# motherboard.net
KiCad netlist of a schematic drawn in EAGLE
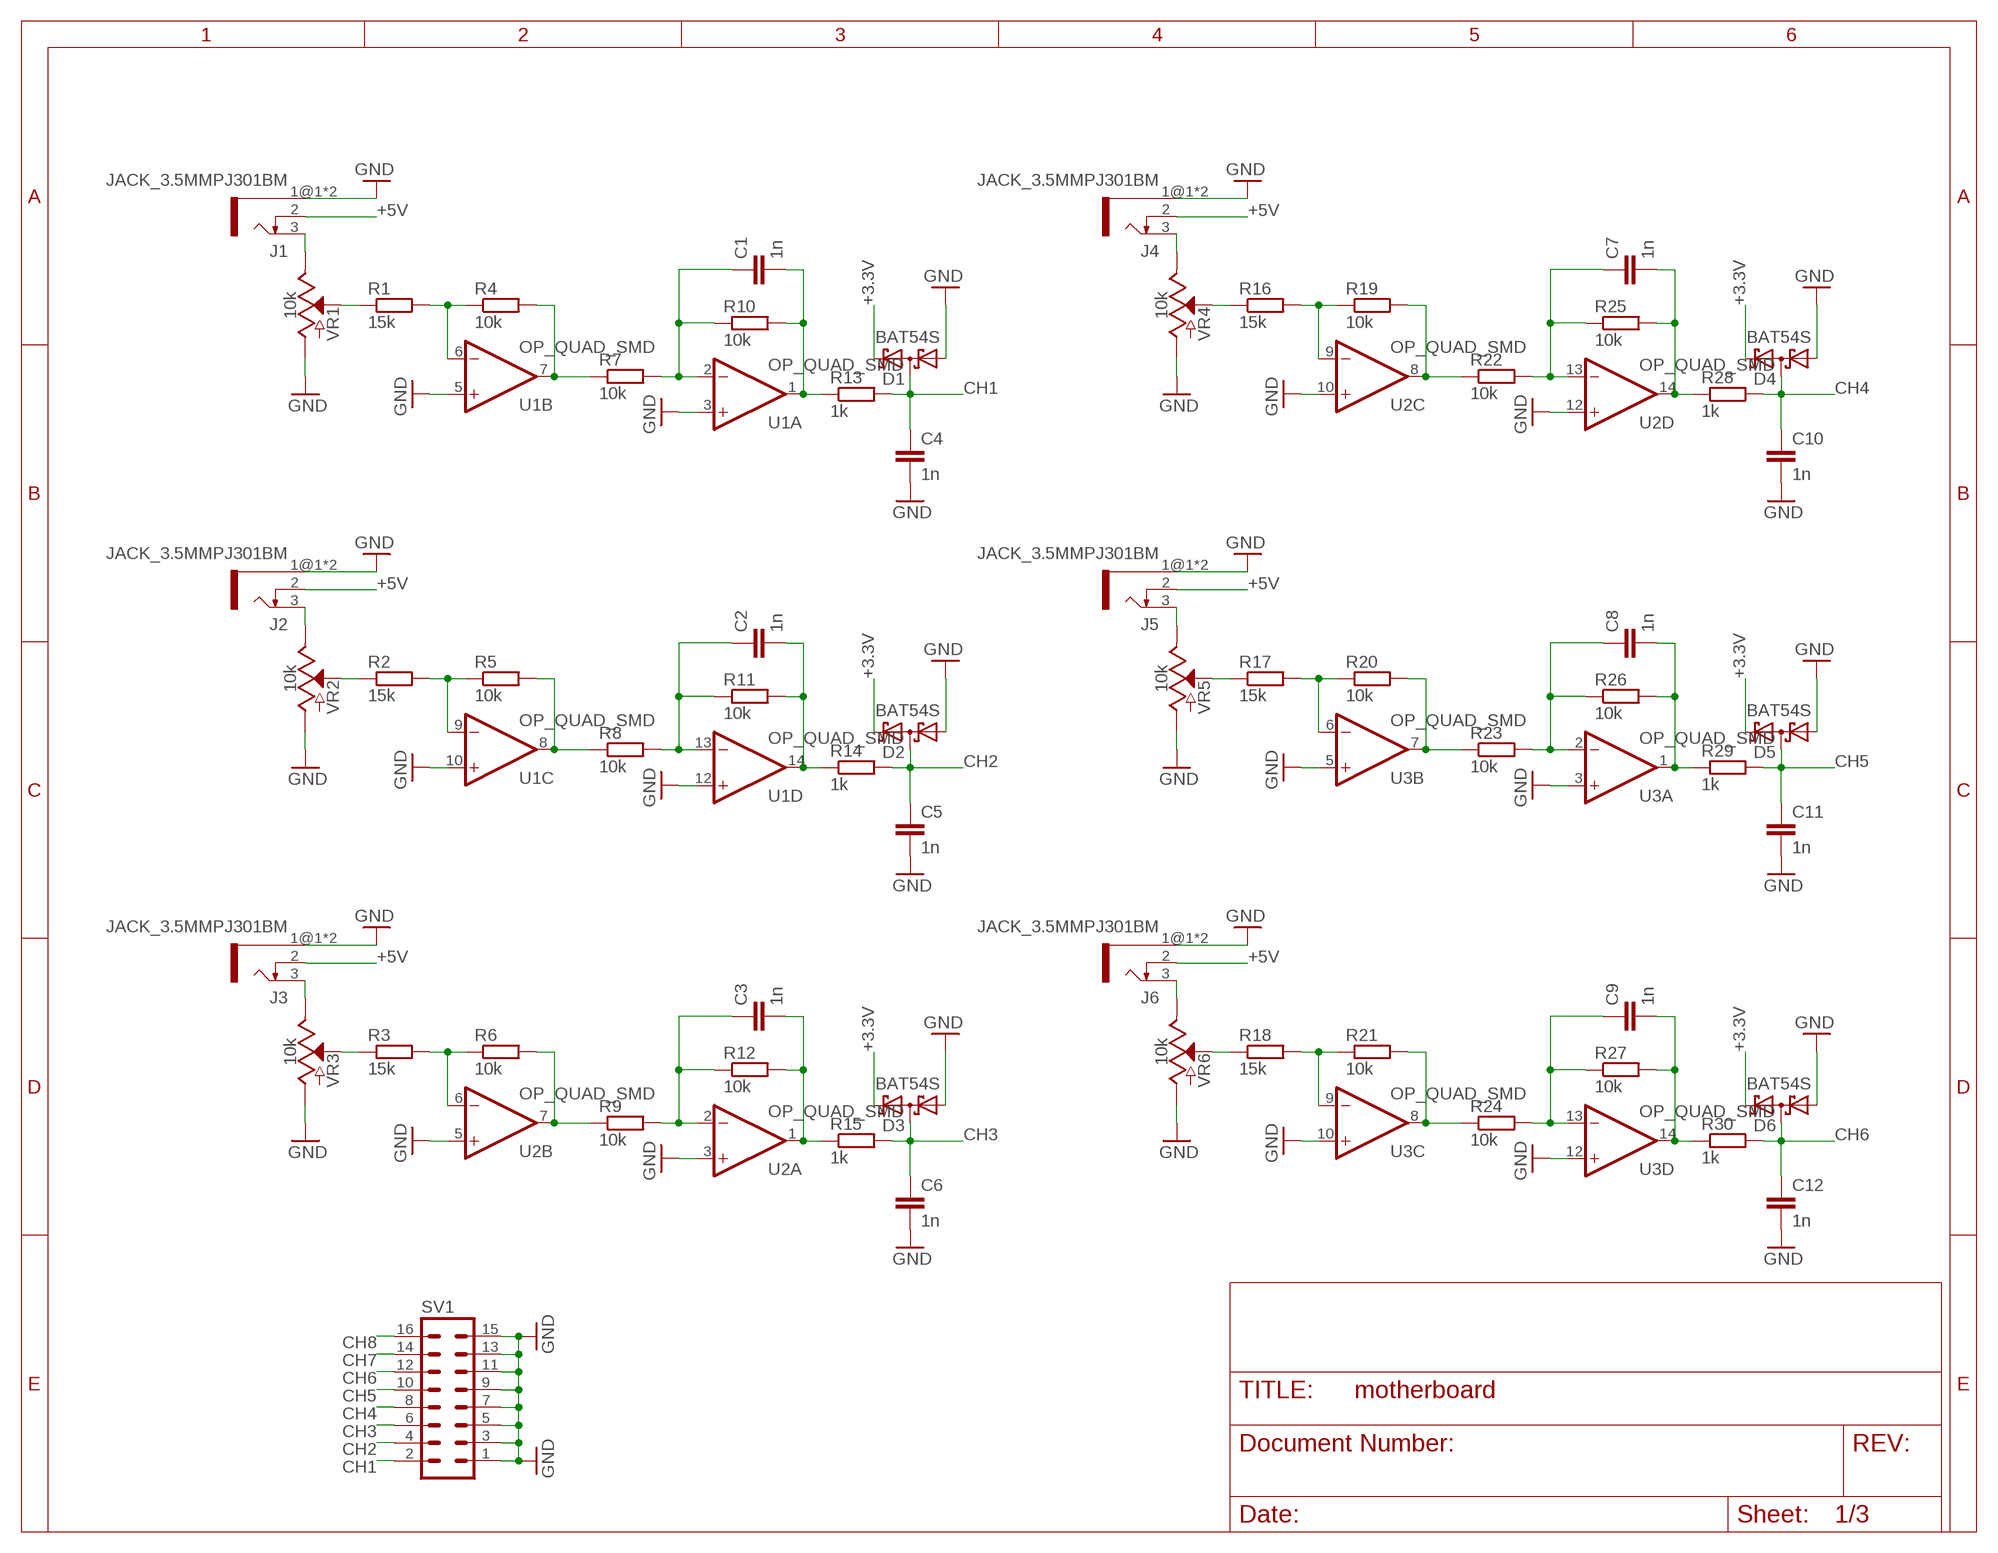
[diagram p0: schematic, sheet 1]
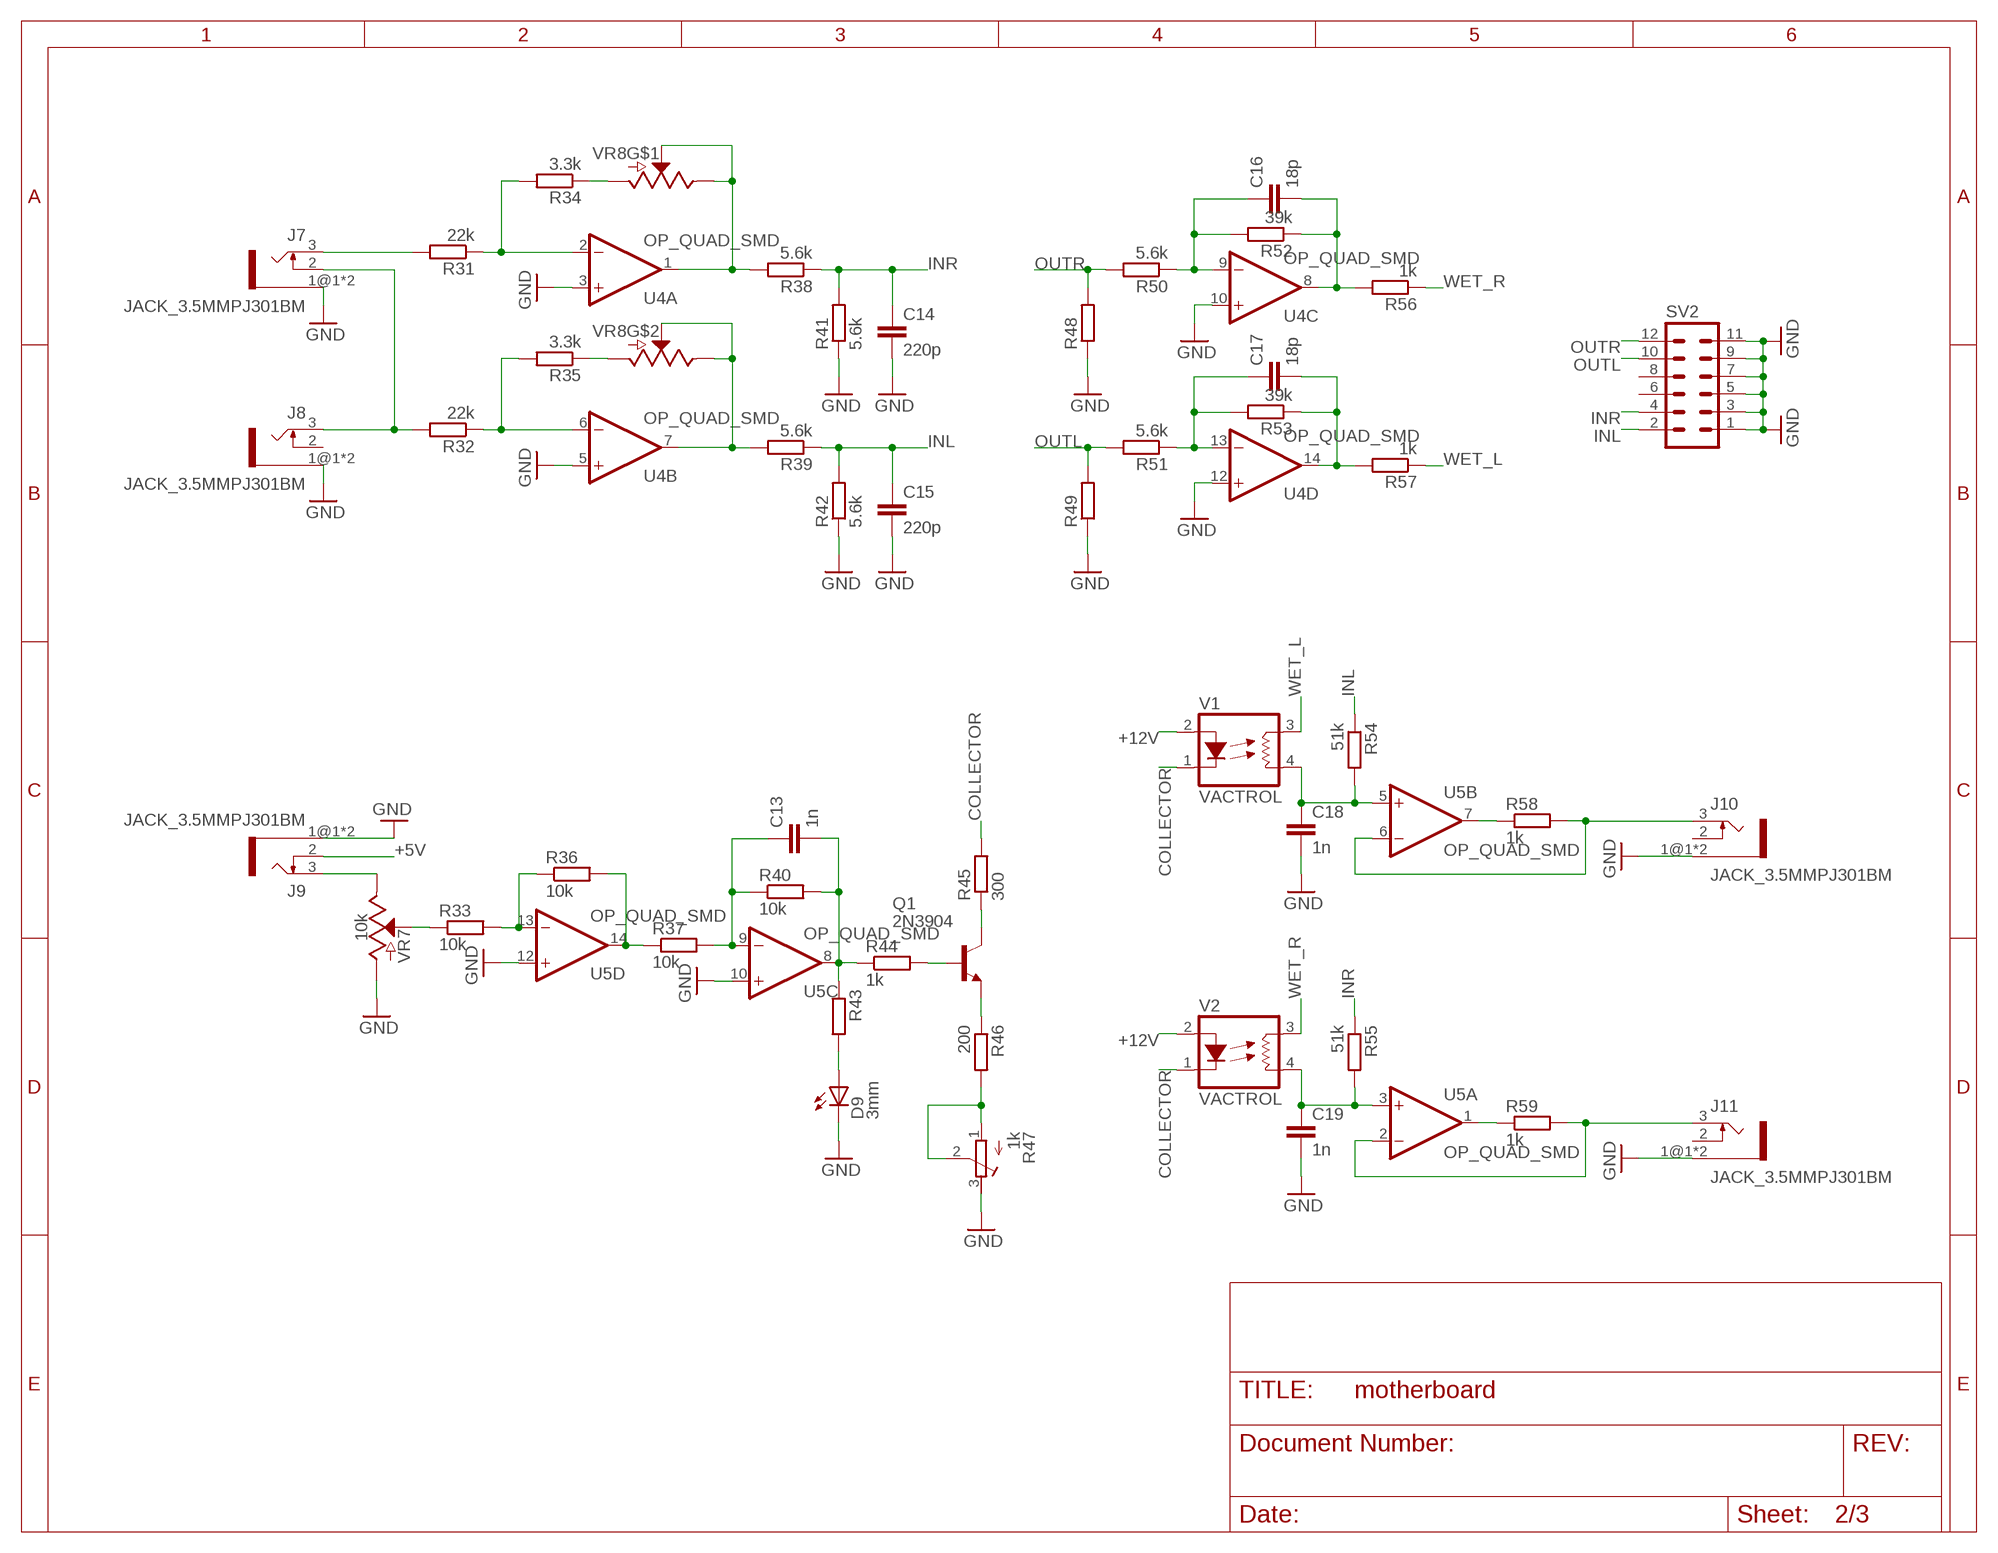
[diagram p1: schematic, sheet 2]
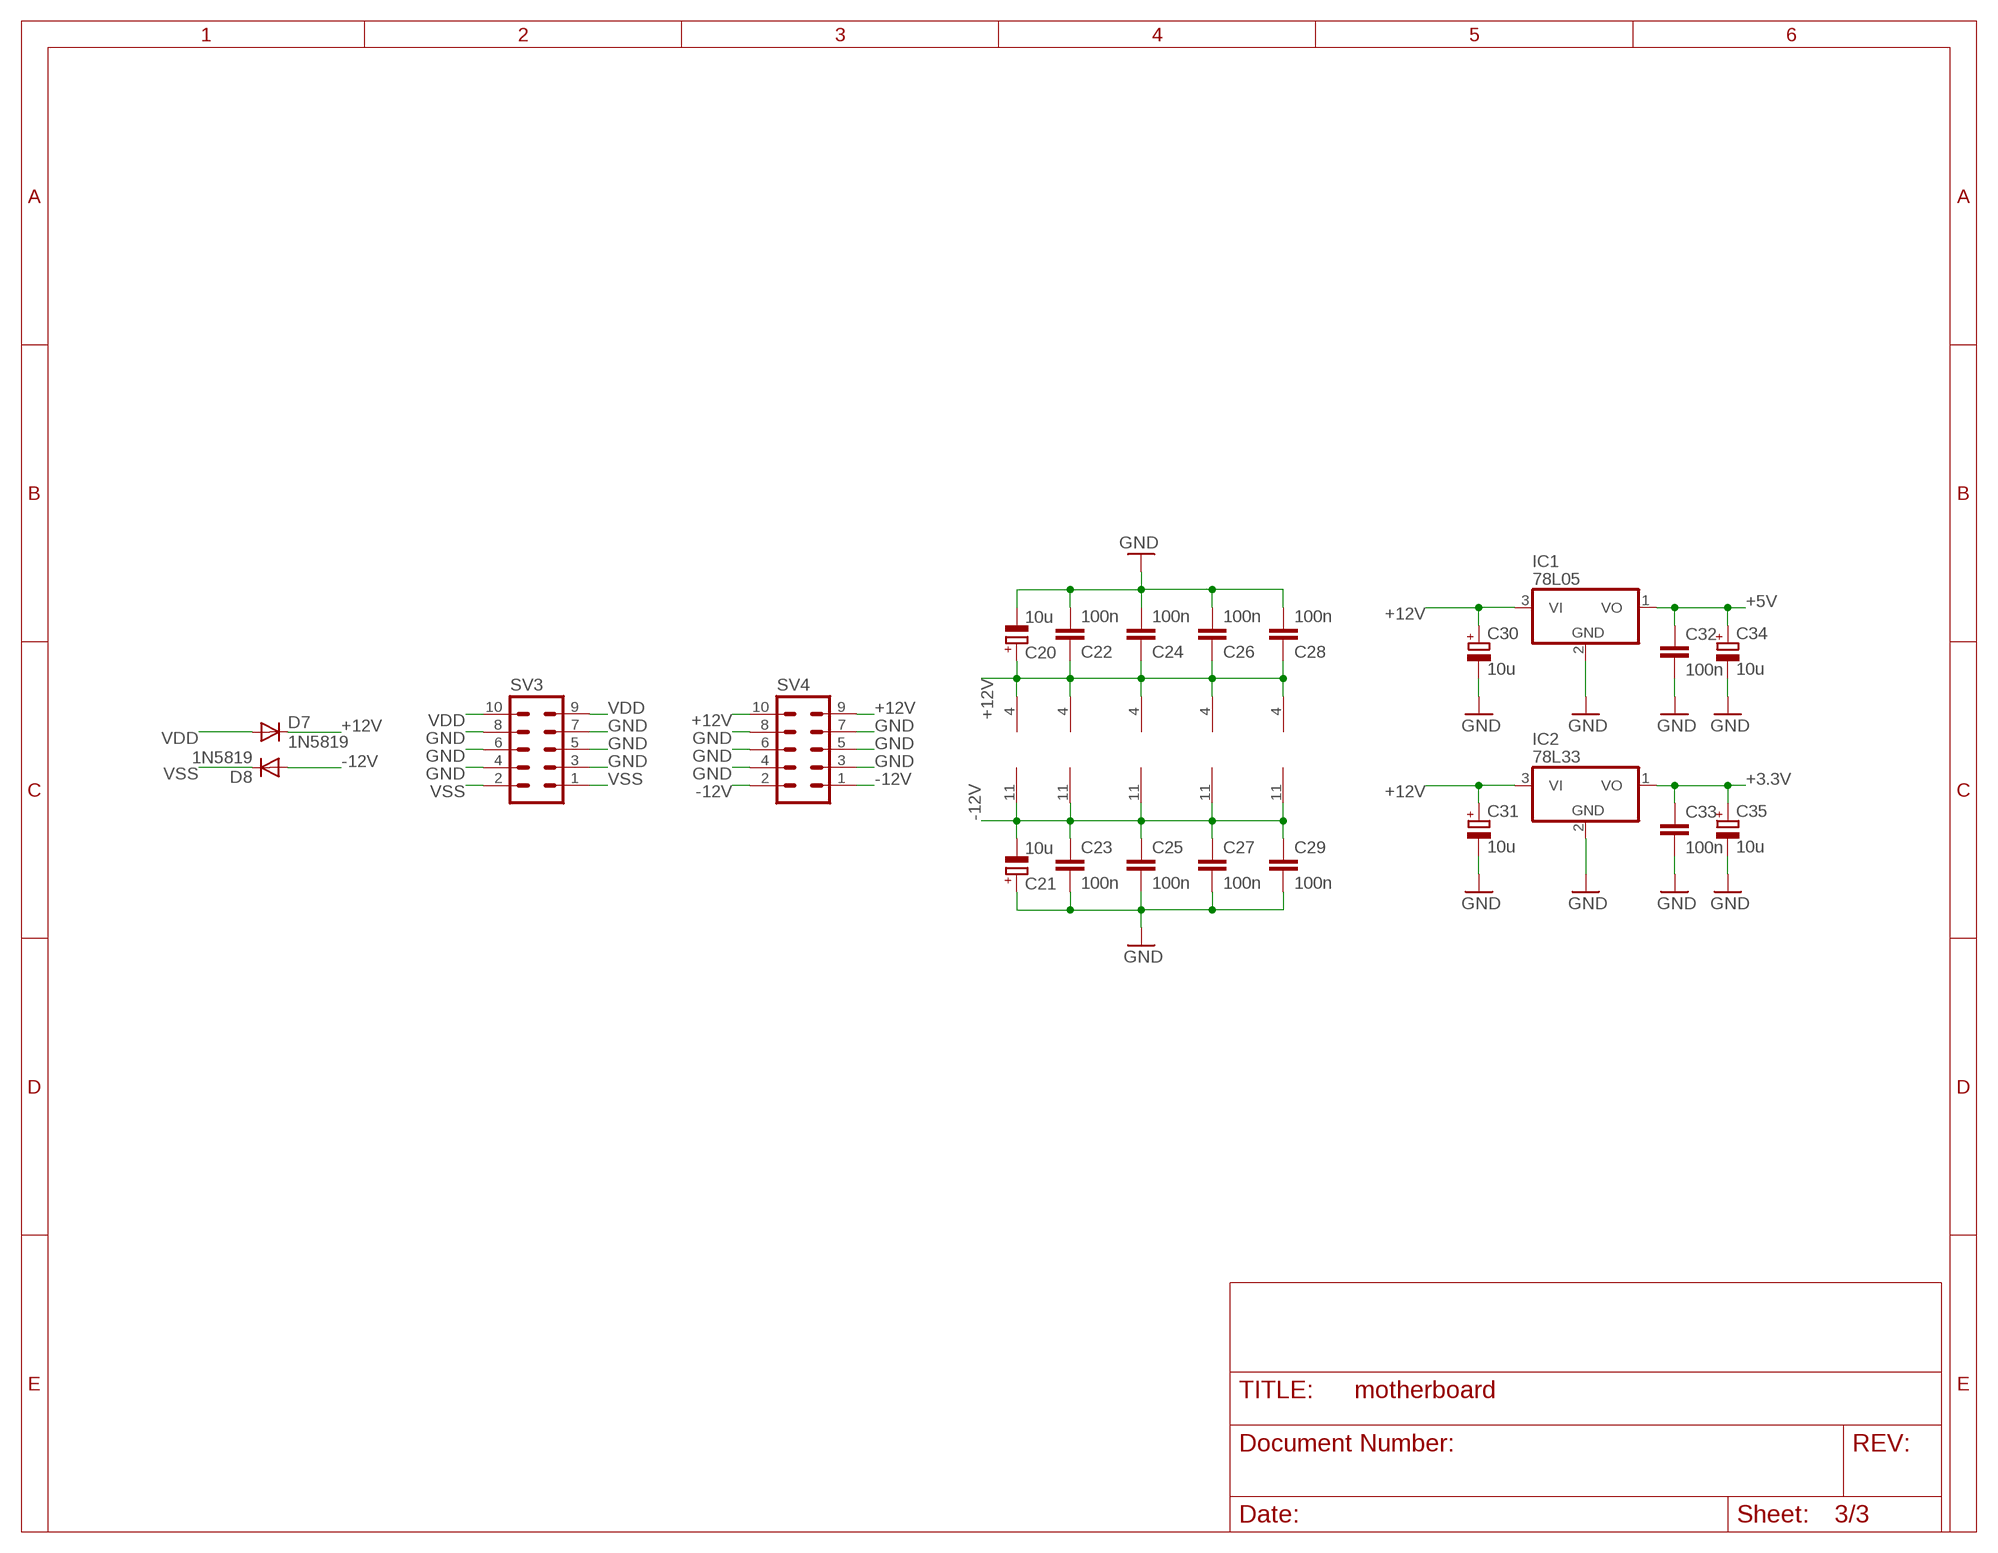
[diagram p2: schematic, sheet 3]

(export (version "E")
  (design (tool "Eeschema 10.0.6"))
  (components
    (comp (ref "C20")
      (value "10u")
      (footprint "eagle-import:E2,5-6")
      (libsource (lib "eagle-import") (part "CPOL-EUE2.5-6"))
    )
    (comp (ref "C21")
      (value "10u")
      (footprint "eagle-import:E2,5-6")
      (libsource (lib "eagle-import") (part "CPOL-EUE2.5-6"))
    )
    (comp (ref "C22")
      (value "100n")
      (footprint "eagle-import:C5B3.5")
      (libsource (lib "eagle-import") (part "C5/3.5"))
    )
    (comp (ref "C23")
      (value "100n")
      (footprint "eagle-import:C5B3.5")
      (libsource (lib "eagle-import") (part "C5/3.5"))
    )
    (comp (ref "C24")
      (value "100n")
      (footprint "eagle-import:C5B3.5")
      (libsource (lib "eagle-import") (part "C5/3.5"))
    )
    (comp (ref "C25")
      (value "100n")
      (footprint "eagle-import:C5B3.5")
      (libsource (lib "eagle-import") (part "C5/3.5"))
    )
    (comp (ref "C26")
      (value "100n")
      (footprint "eagle-import:C5B3.5")
      (libsource (lib "eagle-import") (part "C5/3.5"))
    )
    (comp (ref "C27")
      (value "100n")
      (footprint "eagle-import:C5B3.5")
      (libsource (lib "eagle-import") (part "C5/3.5"))
    )
    (comp (ref "C28")
      (value "100n")
      (footprint "eagle-import:C5B3.5")
      (libsource (lib "eagle-import") (part "C5/3.5"))
    )
    (comp (ref "C29")
      (value "100n")
      (footprint "eagle-import:C5B3.5")
      (libsource (lib "eagle-import") (part "C5/3.5"))
    )
    (comp (ref "C30")
      (value "10u")
      (footprint "eagle-import:E2,5-6")
      (libsource (lib "eagle-import") (part "CPOL-EUE2.5-6"))
    )
    (comp (ref "C31")
      (value "10u")
      (footprint "eagle-import:E2,5-6")
      (libsource (lib "eagle-import") (part "CPOL-EUE2.5-6"))
    )
    (comp (ref "C32")
      (value "100n")
      (footprint "eagle-import:C5B3.5")
      (libsource (lib "eagle-import") (part "C5/3.5"))
    )
    (comp (ref "C33")
      (value "100n")
      (footprint "eagle-import:C5B3.5")
      (libsource (lib "eagle-import") (part "C5/3.5"))
    )
    (comp (ref "C34")
      (value "10u")
      (footprint "eagle-import:E2,5-6")
      (libsource (lib "eagle-import") (part "CPOL-EUE2.5-6"))
    )
    (comp (ref "C35")
      (value "10u")
      (footprint "eagle-import:E2,5-6")
      (libsource (lib "eagle-import") (part "CPOL-EUE2.5-6"))
    )
    (comp (ref "D7")
      (value "1N5819")
      (footprint "eagle-import:SOD-123_MINI-SMA")
      (libsource (lib "eagle-import") (part "CGRM400-G1"))
    )
    (comp (ref "D8")
      (value "1N5819")
      (footprint "eagle-import:SOD-123_MINI-SMA")
      (libsource (lib "eagle-import") (part "CGRM400-G1"))
    )
    (comp (ref "IC1")
      (value "78L05")
      (footprint "eagle-import:TO92")
      (libsource (lib "eagle-import") (part "78ZL05"))
    )
    (comp (ref "IC2")
      (value "78L33")
      (footprint "eagle-import:TO92")
      (libsource (lib "eagle-import") (part "78ZL05"))
    )
    (comp (ref "SV3")
      (value "MA05-2")
      (footprint "eagle-import:MA05-2")
      (libsource (lib "eagle-import") (part "MA05-2"))
    )
    (comp (ref "SV4")
      (value "MA05-2")
      (footprint "eagle-import:MA05-2")
      (libsource (lib "eagle-import") (part "MA05-2"))
    )
    (comp (ref "U1")
      (value "OP_QUAD_SMD")
      (footprint "eagle-import:SO14")
      (libsource (lib "eagle-import") (part "OP_QUAD_SMD"))
    )
    (comp (ref "U2")
      (value "OP_QUAD_SMD")
      (footprint "eagle-import:SO14")
      (libsource (lib "eagle-import") (part "OP_QUAD_SMD"))
    )
    (comp (ref "U3")
      (value "OP_QUAD_SMD")
      (footprint "eagle-import:SO14")
      (libsource (lib "eagle-import") (part "OP_QUAD_SMD"))
    )
    (comp (ref "U4")
      (value "OP_QUAD_SMD")
      (footprint "eagle-import:SO14")
      (libsource (lib "eagle-import") (part "OP_QUAD_SMD"))
    )
    (comp (ref "U5")
      (value "OP_QUAD_SMD")
      (footprint "eagle-import:SO14")
      (libsource (lib "eagle-import") (part "OP_QUAD_SMD"))
    )
    (comp (ref "C1")
      (value "1n")
      (footprint "eagle-import:C0603")
      (libsource (lib "eagle-import") (part "CC0603"))
    )
    (comp (ref "C2")
      (value "1n")
      (footprint "eagle-import:C0603")
      (libsource (lib "eagle-import") (part "CC0603"))
    )
    (comp (ref "C3")
      (value "1n")
      (footprint "eagle-import:C0603")
      (libsource (lib "eagle-import") (part "CC0603"))
    )
    (comp (ref "C4")
      (value "1n")
      (footprint "eagle-import:C0603")
      (libsource (lib "eagle-import") (part "CC0603"))
    )
    (comp (ref "C5")
      (value "1n")
      (footprint "eagle-import:C0603")
      (libsource (lib "eagle-import") (part "CC0603"))
    )
    (comp (ref "C6")
      (value "1n")
      (footprint "eagle-import:C0603")
      (libsource (lib "eagle-import") (part "CC0603"))
    )
    (comp (ref "C7")
      (value "1n")
      (footprint "eagle-import:C0603")
      (libsource (lib "eagle-import") (part "CC0603"))
    )
    (comp (ref "C8")
      (value "1n")
      (footprint "eagle-import:C0603")
      (libsource (lib "eagle-import") (part "CC0603"))
    )
    (comp (ref "C9")
      (value "1n")
      (footprint "eagle-import:C0603")
      (libsource (lib "eagle-import") (part "CC0603"))
    )
    (comp (ref "C10")
      (value "1n")
      (footprint "eagle-import:C0603")
      (libsource (lib "eagle-import") (part "CC0603"))
    )
    (comp (ref "C11")
      (value "1n")
      (footprint "eagle-import:C0603")
      (libsource (lib "eagle-import") (part "CC0603"))
    )
    (comp (ref "C12")
      (value "1n")
      (footprint "eagle-import:C0603")
      (libsource (lib "eagle-import") (part "CC0603"))
    )
    (comp (ref "D1")
      (value "BAT54S")
      (footprint "eagle-import:SOT23")
      (libsource (lib "eagle-import") (part "BAT54S"))
    )
    (comp (ref "D2")
      (value "BAT54S")
      (footprint "eagle-import:SOT23")
      (libsource (lib "eagle-import") (part "BAT54S"))
    )
    (comp (ref "D3")
      (value "BAT54S")
      (footprint "eagle-import:SOT23")
      (libsource (lib "eagle-import") (part "BAT54S"))
    )
    (comp (ref "D4")
      (value "BAT54S")
      (footprint "eagle-import:SOT23")
      (libsource (lib "eagle-import") (part "BAT54S"))
    )
    (comp (ref "D5")
      (value "BAT54S")
      (footprint "eagle-import:SOT23")
      (libsource (lib "eagle-import") (part "BAT54S"))
    )
    (comp (ref "D6")
      (value "BAT54S")
      (footprint "eagle-import:SOT23")
      (libsource (lib "eagle-import") (part "BAT54S"))
    )
    (comp (ref "J1")
      (value "JACK_3.5MMPJ301BM")
      (footprint "eagle-import:PJ301BM_JACK")
      (libsource (lib "eagle-import") (part "JACK_3.5MMPJ301BM"))
    )
    (comp (ref "J2")
      (value "JACK_3.5MMPJ301BM")
      (footprint "eagle-import:PJ301BM_JACK")
      (libsource (lib "eagle-import") (part "JACK_3.5MMPJ301BM"))
    )
    (comp (ref "J3")
      (value "JACK_3.5MMPJ301BM")
      (footprint "eagle-import:PJ301BM_JACK")
      (libsource (lib "eagle-import") (part "JACK_3.5MMPJ301BM"))
    )
    (comp (ref "J4")
      (value "JACK_3.5MMPJ301BM")
      (footprint "eagle-import:PJ301BM_JACK")
      (libsource (lib "eagle-import") (part "JACK_3.5MMPJ301BM"))
    )
    (comp (ref "J5")
      (value "JACK_3.5MMPJ301BM")
      (footprint "eagle-import:PJ301BM_JACK")
      (libsource (lib "eagle-import") (part "JACK_3.5MMPJ301BM"))
    )
    (comp (ref "J6")
      (value "JACK_3.5MMPJ301BM")
      (footprint "eagle-import:PJ301BM_JACK")
      (libsource (lib "eagle-import") (part "JACK_3.5MMPJ301BM"))
    )
    (comp (ref "R1")
      (value "15k")
      (footprint "eagle-import:R0603")
      (libsource (lib "eagle-import") (part "RR0603"))
    )
    (comp (ref "R2")
      (value "15k")
      (footprint "eagle-import:R0603")
      (libsource (lib "eagle-import") (part "RR0603"))
    )
    (comp (ref "R3")
      (value "15k")
      (footprint "eagle-import:R0603")
      (libsource (lib "eagle-import") (part "RR0603"))
    )
    (comp (ref "R4")
      (value "10k")
      (footprint "eagle-import:R0603")
      (libsource (lib "eagle-import") (part "RR0603"))
    )
    (comp (ref "R5")
      (value "10k")
      (footprint "eagle-import:R0603")
      (libsource (lib "eagle-import") (part "RR0603"))
    )
    (comp (ref "R6")
      (value "10k")
      (footprint "eagle-import:R0603")
      (libsource (lib "eagle-import") (part "RR0603"))
    )
    (comp (ref "R7")
      (value "10k")
      (footprint "eagle-import:R0603")
      (libsource (lib "eagle-import") (part "RR0603"))
    )
    (comp (ref "R8")
      (value "10k")
      (footprint "eagle-import:R0603")
      (libsource (lib "eagle-import") (part "RR0603"))
    )
    (comp (ref "R9")
      (value "10k")
      (footprint "eagle-import:R0603")
      (libsource (lib "eagle-import") (part "RR0603"))
    )
    (comp (ref "R10")
      (value "10k")
      (footprint "eagle-import:R0603")
      (libsource (lib "eagle-import") (part "RR0603"))
    )
    (comp (ref "R11")
      (value "10k")
      (footprint "eagle-import:R0603")
      (libsource (lib "eagle-import") (part "RR0603"))
    )
    (comp (ref "R12")
      (value "10k")
      (footprint "eagle-import:R0603")
      (libsource (lib "eagle-import") (part "RR0603"))
    )
    (comp (ref "R13")
      (value "1k")
      (footprint "eagle-import:R0603")
      (libsource (lib "eagle-import") (part "RR0603"))
    )
    (comp (ref "R14")
      (value "1k")
      (footprint "eagle-import:R0603")
      (libsource (lib "eagle-import") (part "RR0603"))
    )
    (comp (ref "R15")
      (value "1k")
      (footprint "eagle-import:R0603")
      (libsource (lib "eagle-import") (part "RR0603"))
    )
    (comp (ref "R16")
      (value "15k")
      (footprint "eagle-import:R0603")
      (libsource (lib "eagle-import") (part "RR0603"))
    )
    (comp (ref "R17")
      (value "15k")
      (footprint "eagle-import:R0603")
      (libsource (lib "eagle-import") (part "RR0603"))
    )
    (comp (ref "R18")
      (value "15k")
      (footprint "eagle-import:R0603")
      (libsource (lib "eagle-import") (part "RR0603"))
    )
    (comp (ref "R19")
      (value "10k")
      (footprint "eagle-import:R0603")
      (libsource (lib "eagle-import") (part "RR0603"))
    )
    (comp (ref "R20")
      (value "10k")
      (footprint "eagle-import:R0603")
      (libsource (lib "eagle-import") (part "RR0603"))
    )
    (comp (ref "R21")
      (value "10k")
      (footprint "eagle-import:R0603")
      (libsource (lib "eagle-import") (part "RR0603"))
    )
    (comp (ref "R22")
      (value "10k")
      (footprint "eagle-import:R0603")
      (libsource (lib "eagle-import") (part "RR0603"))
    )
    (comp (ref "R23")
      (value "10k")
      (footprint "eagle-import:R0603")
      (libsource (lib "eagle-import") (part "RR0603"))
    )
    (comp (ref "R24")
      (value "10k")
      (footprint "eagle-import:R0603")
      (libsource (lib "eagle-import") (part "RR0603"))
    )
    (comp (ref "R25")
      (value "10k")
      (footprint "eagle-import:R0603")
      (libsource (lib "eagle-import") (part "RR0603"))
    )
    (comp (ref "R26")
      (value "10k")
      (footprint "eagle-import:R0603")
      (libsource (lib "eagle-import") (part "RR0603"))
    )
    (comp (ref "R27")
      (value "10k")
      (footprint "eagle-import:R0603")
      (libsource (lib "eagle-import") (part "RR0603"))
    )
    (comp (ref "R28")
      (value "1k")
      (footprint "eagle-import:R0603")
      (libsource (lib "eagle-import") (part "RR0603"))
    )
    (comp (ref "R29")
      (value "1k")
      (footprint "eagle-import:R0603")
      (libsource (lib "eagle-import") (part "RR0603"))
    )
    (comp (ref "R30")
      (value "1k")
      (footprint "eagle-import:R0603")
      (libsource (lib "eagle-import") (part "RR0603"))
    )
    (comp (ref "SV1")
      (value "MA08-2")
      (footprint "eagle-import:MA08-2")
      (libsource (lib "eagle-import") (part "MA08-2"))
    )
    (comp (ref "VR1")
      (value "10k")
      (footprint "eagle-import:POT-PTH-ALPS-KIT")
      (libsource (lib "eagle-import") (part "POTENTIOMETER-PTH-9MM-1/20W-20%-KIT"))
    )
    (comp (ref "VR2")
      (value "10k")
      (footprint "eagle-import:POT-PTH-ALPS-KIT")
      (libsource (lib "eagle-import") (part "POTENTIOMETER-PTH-9MM-1/20W-20%-KIT"))
    )
    (comp (ref "VR3")
      (value "10k")
      (footprint "eagle-import:POT-PTH-ALPS-KIT")
      (libsource (lib "eagle-import") (part "POTENTIOMETER-PTH-9MM-1/20W-20%-KIT"))
    )
    (comp (ref "VR4")
      (value "10k")
      (footprint "eagle-import:POT-PTH-ALPS-KIT")
      (libsource (lib "eagle-import") (part "POTENTIOMETER-PTH-9MM-1/20W-20%-KIT"))
    )
    (comp (ref "VR5")
      (value "10k")
      (footprint "eagle-import:POT-PTH-ALPS-KIT")
      (libsource (lib "eagle-import") (part "POTENTIOMETER-PTH-9MM-1/20W-20%-KIT"))
    )
    (comp (ref "VR6")
      (value "10k")
      (footprint "eagle-import:POT-PTH-ALPS-KIT")
      (libsource (lib "eagle-import") (part "POTENTIOMETER-PTH-9MM-1/20W-20%-KIT"))
    )
    (comp (ref "C13")
      (value "1n")
      (footprint "eagle-import:C0603")
      (libsource (lib "eagle-import") (part "CC0603"))
    )
    (comp (ref "C14")
      (value "220p")
      (footprint "eagle-import:C0603")
      (libsource (lib "eagle-import") (part "CC0603"))
    )
    (comp (ref "C15")
      (value "220p")
      (footprint "eagle-import:C0603")
      (libsource (lib "eagle-import") (part "CC0603"))
    )
    (comp (ref "C16")
      (value "18p")
      (footprint "eagle-import:C0603")
      (libsource (lib "eagle-import") (part "CC0603"))
    )
    (comp (ref "C17")
      (value "18p")
      (footprint "eagle-import:C0603")
      (libsource (lib "eagle-import") (part "CC0603"))
    )
    (comp (ref "C18")
      (value "1n")
      (footprint "eagle-import:C0603")
      (libsource (lib "eagle-import") (part "CC0603"))
    )
    (comp (ref "C19")
      (value "1n")
      (footprint "eagle-import:C0603")
      (libsource (lib "eagle-import") (part "CC0603"))
    )
    (comp (ref "D9")
      (value "3mm")
      (footprint "eagle-import:LED3MM")
      (libsource (lib "eagle-import") (part "LED3MM"))
    )
    (comp (ref "J7")
      (value "JACK_3.5MMPJ301BM")
      (footprint "eagle-import:PJ301BM_JACK")
      (libsource (lib "eagle-import") (part "JACK_3.5MMPJ301BM"))
    )
    (comp (ref "J8")
      (value "JACK_3.5MMPJ301BM")
      (footprint "eagle-import:PJ301BM_JACK")
      (libsource (lib "eagle-import") (part "JACK_3.5MMPJ301BM"))
    )
    (comp (ref "J9")
      (value "JACK_3.5MMPJ301BM")
      (footprint "eagle-import:PJ301BM_JACK")
      (libsource (lib "eagle-import") (part "JACK_3.5MMPJ301BM"))
    )
    (comp (ref "J10")
      (value "JACK_3.5MMPJ301BM")
      (footprint "eagle-import:PJ301BM_JACK")
      (libsource (lib "eagle-import") (part "JACK_3.5MMPJ301BM"))
    )
    (comp (ref "J11")
      (value "JACK_3.5MMPJ301BM")
      (footprint "eagle-import:PJ301BM_JACK")
      (libsource (lib "eagle-import") (part "JACK_3.5MMPJ301BM"))
    )
    (comp (ref "Q1")
      (value "2N3904")
      (footprint "eagle-import:TO92")
      (libsource (lib "eagle-import") (part "2N3904"))
    )
    (comp (ref "R31")
      (value "22k")
      (footprint "eagle-import:R0603")
      (libsource (lib "eagle-import") (part "RR0603"))
    )
    (comp (ref "R32")
      (value "22k")
      (footprint "eagle-import:R0603")
      (libsource (lib "eagle-import") (part "RR0603"))
    )
    (comp (ref "R33")
      (value "10k")
      (footprint "eagle-import:R0603")
      (libsource (lib "eagle-import") (part "RR0603"))
    )
    (comp (ref "R34")
      (value "3.3k")
      (footprint "eagle-import:R0603")
      (libsource (lib "eagle-import") (part "RR0603"))
    )
    (comp (ref "R35")
      (value "3.3k")
      (footprint "eagle-import:R0603")
      (libsource (lib "eagle-import") (part "RR0603"))
    )
    (comp (ref "R36")
      (value "10k")
      (footprint "eagle-import:R0603")
      (libsource (lib "eagle-import") (part "RR0603"))
    )
    (comp (ref "R37")
      (value "10k")
      (footprint "eagle-import:R0603")
      (libsource (lib "eagle-import") (part "RR0603"))
    )
    (comp (ref "R38")
      (value "5.6k")
      (footprint "eagle-import:R0603")
      (libsource (lib "eagle-import") (part "RR0603"))
    )
    (comp (ref "R39")
      (value "5.6k")
      (footprint "eagle-import:R0603")
      (libsource (lib "eagle-import") (part "RR0603"))
    )
    (comp (ref "R40")
      (value "10k")
      (footprint "eagle-import:R0603")
      (libsource (lib "eagle-import") (part "RR0603"))
    )
    (comp (ref "R41")
      (value "5.6k")
      (footprint "eagle-import:R0603")
      (libsource (lib "eagle-import") (part "RR0603"))
    )
    (comp (ref "R42")
      (value "5.6k")
      (footprint "eagle-import:R0603")
      (libsource (lib "eagle-import") (part "RR0603"))
    )
    (comp (ref "R43")
      (value "RESISTOR10MM")
      (footprint "eagle-import:1_4W_RESISTOR")
      (libsource (lib "eagle-import") (part "RESISTOR10MM"))
    )
    (comp (ref "R44")
      (value "1k")
      (footprint "eagle-import:R0603")
      (libsource (lib "eagle-import") (part "RR0603"))
    )
    (comp (ref "R45")
      (value "300")
      (footprint "eagle-import:1_4W_RESISTOR")
      (libsource (lib "eagle-import") (part "RESISTOR10MM"))
    )
    (comp (ref "R46")
      (value "200")
      (footprint "eagle-import:R0603")
      (libsource (lib "eagle-import") (part "RR0603"))
    )
    (comp (ref "R47")
      (value "1k")
      (footprint "eagle-import:RTRIM64W")
      (libsource (lib "eagle-import") (part "R-TRIMM64W"))
    )
    (comp (ref "R48")
      (value "RR0603")
      (footprint "eagle-import:R0603")
      (libsource (lib "eagle-import") (part "RR0603"))
    )
    (comp (ref "R49")
      (value "RR0603")
      (footprint "eagle-import:R0603")
      (libsource (lib "eagle-import") (part "RR0603"))
    )
    (comp (ref "R50")
      (value "5.6k")
      (footprint "eagle-import:R0603")
      (libsource (lib "eagle-import") (part "RR0603"))
    )
    (comp (ref "R51")
      (value "5.6k")
      (footprint "eagle-import:R0603")
      (libsource (lib "eagle-import") (part "RR0603"))
    )
    (comp (ref "R52")
      (value "39k")
      (footprint "eagle-import:R0603")
      (libsource (lib "eagle-import") (part "RR0603"))
    )
    (comp (ref "R53")
      (value "39k")
      (footprint "eagle-import:R0603")
      (libsource (lib "eagle-import") (part "RR0603"))
    )
    (comp (ref "R54")
      (value "51k")
      (footprint "eagle-import:R0603")
      (libsource (lib "eagle-import") (part "RR0603"))
    )
    (comp (ref "R55")
      (value "51k")
      (footprint "eagle-import:R0603")
      (libsource (lib "eagle-import") (part "RR0603"))
    )
    (comp (ref "R56")
      (value "1k")
      (footprint "eagle-import:R0603")
      (libsource (lib "eagle-import") (part "RR0603"))
    )
    (comp (ref "R57")
      (value "1k")
      (footprint "eagle-import:R0603")
      (libsource (lib "eagle-import") (part "RR0603"))
    )
    (comp (ref "R58")
      (value "1k")
      (footprint "eagle-import:R0603")
      (libsource (lib "eagle-import") (part "RR0603"))
    )
    (comp (ref "R59")
      (value "1k")
      (footprint "eagle-import:R0603")
      (libsource (lib "eagle-import") (part "RR0603"))
    )
    (comp (ref "SV2")
      (value "MA06-2")
      (footprint "eagle-import:MA06-2")
      (libsource (lib "eagle-import") (part "MA06-2"))
    )
    (comp (ref "V1")
      (value "VACTROL")
      (footprint "eagle-import:VACTROL_4PIN_VTL5C")
      (libsource (lib "eagle-import") (part "VACTROL"))
    )
    (comp (ref "V2")
      (value "VACTROL")
      (footprint "eagle-import:VACTROL_4PIN_VTL5C")
      (libsource (lib "eagle-import") (part "VACTROL"))
    )
    (comp (ref "VR7")
      (value "10k")
      (footprint "eagle-import:POT-PTH-ALPS-KIT")
      (libsource (lib "eagle-import") (part "POTENTIOMETER-PTH-9MM-1/20W-20%-KIT"))
    )
    (comp (ref "VR8")
      (value "POTENTIOMETER_DUAL-PTH-12MM-1/20W-20%-KIT")
      (footprint "eagle-import:POT-DUAL-PTH-PANASONIC-VERT-KIT")
      (libsource (lib "eagle-import") (part "POTENTIOMETER_DUAL-PTH-12MM-1/20W-20%-KIT"))
    )
  )
  (nets
    (net (code "1") (name "+3.3V") (class "Default")
      (node (ref "C33") (pin "1") (pinfunction "1_1") (pintype "passive"))
      (node (ref "C35") (pin "+") (pinfunction "+_+") (pintype "passive"))
      (node (ref "D1") (pin "2") (pinfunction "C2_2") (pintype "passive"))
      (node (ref "D2") (pin "2") (pinfunction "C2_2") (pintype "passive"))
      (node (ref "D3") (pin "2") (pinfunction "C2_2") (pintype "passive"))
      (node (ref "D4") (pin "2") (pinfunction "C2_2") (pintype "passive"))
      (node (ref "D5") (pin "2") (pinfunction "C2_2") (pintype "passive"))
      (node (ref "D6") (pin "2") (pinfunction "C2_2") (pintype "passive"))
      (node (ref "IC2") (pin "1") (pinfunction "VO_1") (pintype "passive"))
    )
    (net (code "2") (name "+5V") (class "Default")
      (node (ref "C32") (pin "1") (pinfunction "1_1") (pintype "passive"))
      (node (ref "C34") (pin "+") (pinfunction "+_+") (pintype "passive"))
      (node (ref "IC1") (pin "1") (pinfunction "VO_1") (pintype "passive"))
      (node (ref "J1") (pin "2") (pinfunction "2_2") (pintype "passive"))
      (node (ref "J2") (pin "2") (pinfunction "2_2") (pintype "passive"))
      (node (ref "J3") (pin "2") (pinfunction "2_2") (pintype "passive"))
      (node (ref "J4") (pin "2") (pinfunction "2_2") (pintype "passive"))
      (node (ref "J5") (pin "2") (pinfunction "2_2") (pintype "passive"))
      (node (ref "J6") (pin "2") (pinfunction "2_2") (pintype "passive"))
      (node (ref "J9") (pin "2") (pinfunction "2_2") (pintype "passive"))
    )
    (net (code "3") (name "+12V") (class "Default")
      (node (ref "C20") (pin "+") (pinfunction "+_+") (pintype "passive"))
      (node (ref "C22") (pin "1") (pinfunction "1_1") (pintype "passive"))
      (node (ref "C24") (pin "1") (pinfunction "1_1") (pintype "passive"))
      (node (ref "C26") (pin "1") (pinfunction "1_1") (pintype "passive"))
      (node (ref "C28") (pin "1") (pinfunction "1_1") (pintype "passive"))
      (node (ref "C30") (pin "+") (pinfunction "+_+") (pintype "passive"))
      (node (ref "C31") (pin "+") (pinfunction "+_+") (pintype "passive"))
      (node (ref "D7") (pin "C") (pinfunction "C_C") (pintype "passive"))
      (node (ref "IC1") (pin "3") (pinfunction "VI_3") (pintype "input"))
      (node (ref "IC2") (pin "3") (pinfunction "VI_3") (pintype "input"))
      (node (ref "SV4") (pin "10") (pinfunction "10_10") (pintype "passive"))
      (node (ref "SV4") (pin "9") (pinfunction "9_9") (pintype "passive"))
      (node (ref "U1") (pin "4") (pinfunction "V+_4") (pintype "power_in"))
      (node (ref "U2") (pin "4") (pinfunction "V+_4") (pintype "power_in"))
      (node (ref "U3") (pin "4") (pinfunction "V+_4") (pintype "power_in"))
      (node (ref "U4") (pin "4") (pinfunction "V+_4") (pintype "power_in"))
      (node (ref "U5") (pin "4") (pinfunction "V+_4") (pintype "power_in"))
      (node (ref "V1") (pin "2") (pinfunction "LED+_2") (pintype "passive"))
      (node (ref "V2") (pin "2") (pinfunction "LED+_2") (pintype "passive"))
    )
    (net (code "4") (name "-12V") (class "Default")
      (node (ref "C21") (pin "-") (pinfunction "-_-") (pintype "passive"))
      (node (ref "C23") (pin "1") (pinfunction "1_1") (pintype "passive"))
      (node (ref "C25") (pin "1") (pinfunction "1_1") (pintype "passive"))
      (node (ref "C27") (pin "1") (pinfunction "1_1") (pintype "passive"))
      (node (ref "C29") (pin "1") (pinfunction "1_1") (pintype "passive"))
      (node (ref "D8") (pin "A") (pinfunction "A_A") (pintype "passive"))
      (node (ref "SV4") (pin "1") (pinfunction "1_1") (pintype "passive"))
      (node (ref "SV4") (pin "2") (pinfunction "2_2") (pintype "passive"))
      (node (ref "U1") (pin "11") (pinfunction "V-_11") (pintype "power_in"))
      (node (ref "U2") (pin "11") (pinfunction "V-_11") (pintype "power_in"))
      (node (ref "U3") (pin "11") (pinfunction "V-_11") (pintype "power_in"))
      (node (ref "U4") (pin "11") (pinfunction "V-_11") (pintype "power_in"))
      (node (ref "U5") (pin "11") (pinfunction "V-_11") (pintype "power_in"))
    )
    (net (code "5") (name "CH1") (class "Default")
      (node (ref "C4") (pin "1") (pinfunction "1_1") (pintype "passive"))
      (node (ref "D1") (pin "3") (pinfunction "C1A2_3") (pintype "passive"))
      (node (ref "R13") (pin "2") (pinfunction "2_2") (pintype "passive"))
      (node (ref "SV1") (pin "2") (pinfunction "2_2") (pintype "passive"))
    )
    (net (code "6") (name "CH2") (class "Default")
      (node (ref "C5") (pin "1") (pinfunction "1_1") (pintype "passive"))
      (node (ref "D2") (pin "3") (pinfunction "C1A2_3") (pintype "passive"))
      (node (ref "R14") (pin "2") (pinfunction "2_2") (pintype "passive"))
      (node (ref "SV1") (pin "4") (pinfunction "4_4") (pintype "passive"))
    )
    (net (code "7") (name "CH3") (class "Default")
      (node (ref "C6") (pin "1") (pinfunction "1_1") (pintype "passive"))
      (node (ref "D3") (pin "3") (pinfunction "C1A2_3") (pintype "passive"))
      (node (ref "R15") (pin "2") (pinfunction "2_2") (pintype "passive"))
      (node (ref "SV1") (pin "6") (pinfunction "6_6") (pintype "passive"))
    )
    (net (code "8") (name "CH4") (class "Default")
      (node (ref "C10") (pin "1") (pinfunction "1_1") (pintype "passive"))
      (node (ref "D4") (pin "3") (pinfunction "C1A2_3") (pintype "passive"))
      (node (ref "R28") (pin "2") (pinfunction "2_2") (pintype "passive"))
      (node (ref "SV1") (pin "8") (pinfunction "8_8") (pintype "passive"))
    )
    (net (code "9") (name "CH5") (class "Default")
      (node (ref "C11") (pin "1") (pinfunction "1_1") (pintype "passive"))
      (node (ref "D5") (pin "3") (pinfunction "C1A2_3") (pintype "passive"))
      (node (ref "R29") (pin "2") (pinfunction "2_2") (pintype "passive"))
      (node (ref "SV1") (pin "10") (pinfunction "10_10") (pintype "passive"))
    )
    (net (code "10") (name "CH6") (class "Default")
      (node (ref "C12") (pin "1") (pinfunction "1_1") (pintype "passive"))
      (node (ref "D6") (pin "3") (pinfunction "C1A2_3") (pintype "passive"))
      (node (ref "R30") (pin "2") (pinfunction "2_2") (pintype "passive"))
      (node (ref "SV1") (pin "12") (pinfunction "12_12") (pintype "passive"))
    )
    (net (code "11") (name "CH7") (class "Default")
      (node (ref "SV1") (pin "14") (pinfunction "14_14") (pintype "passive"))
    )
    (net (code "12") (name "CH8") (class "Default")
      (node (ref "SV1") (pin "16") (pinfunction "16_16") (pintype "passive"))
    )
    (net (code "13") (name "COLLECTOR") (class "Default")
      (node (ref "R45") (pin "2") (pinfunction "2_2") (pintype "passive"))
      (node (ref "V1") (pin "1") (pinfunction "LED-_1") (pintype "passive"))
      (node (ref "V2") (pin "1") (pinfunction "LED-_1") (pintype "passive"))
    )
    (net (code "14") (name "GND") (class "Default")
      (node (ref "C10") (pin "2") (pinfunction "2_2") (pintype "passive"))
      (node (ref "C11") (pin "2") (pinfunction "2_2") (pintype "passive"))
      (node (ref "C12") (pin "2") (pinfunction "2_2") (pintype "passive"))
      (node (ref "C14") (pin "2") (pinfunction "2_2") (pintype "passive"))
      (node (ref "C15") (pin "2") (pinfunction "2_2") (pintype "passive"))
      (node (ref "C18") (pin "2") (pinfunction "2_2") (pintype "passive"))
      (node (ref "C19") (pin "2") (pinfunction "2_2") (pintype "passive"))
      (node (ref "C20") (pin "-") (pinfunction "-_-") (pintype "passive"))
      (node (ref "C21") (pin "+") (pinfunction "+_+") (pintype "passive"))
      (node (ref "C22") (pin "2") (pinfunction "2_2") (pintype "passive"))
      (node (ref "C23") (pin "2") (pinfunction "2_2") (pintype "passive"))
      (node (ref "C24") (pin "2") (pinfunction "2_2") (pintype "passive"))
      (node (ref "C25") (pin "2") (pinfunction "2_2") (pintype "passive"))
      (node (ref "C26") (pin "2") (pinfunction "2_2") (pintype "passive"))
      (node (ref "C27") (pin "2") (pinfunction "2_2") (pintype "passive"))
      (node (ref "C28") (pin "2") (pinfunction "2_2") (pintype "passive"))
      (node (ref "C29") (pin "2") (pinfunction "2_2") (pintype "passive"))
      (node (ref "C30") (pin "-") (pinfunction "-_-") (pintype "passive"))
      (node (ref "C31") (pin "-") (pinfunction "-_-") (pintype "passive"))
      (node (ref "C32") (pin "2") (pinfunction "2_2") (pintype "passive"))
      (node (ref "C33") (pin "2") (pinfunction "2_2") (pintype "passive"))
      (node (ref "C34") (pin "-") (pinfunction "-_-") (pintype "passive"))
      (node (ref "C35") (pin "-") (pinfunction "-_-") (pintype "passive"))
      (node (ref "C4") (pin "2") (pinfunction "2_2") (pintype "passive"))
      (node (ref "C5") (pin "2") (pinfunction "2_2") (pintype "passive"))
      (node (ref "C6") (pin "2") (pinfunction "2_2") (pintype "passive"))
      (node (ref "D1") (pin "1") (pinfunction "A1_1") (pintype "passive"))
      (node (ref "D2") (pin "1") (pinfunction "A1_1") (pintype "passive"))
      (node (ref "D3") (pin "1") (pinfunction "A1_1") (pintype "passive"))
      (node (ref "D4") (pin "1") (pinfunction "A1_1") (pintype "passive"))
      (node (ref "D5") (pin "1") (pinfunction "A1_1") (pintype "passive"))
      (node (ref "D6") (pin "1") (pinfunction "A1_1") (pintype "passive"))
      (node (ref "D9") (pin "K") (pinfunction "C_K") (pintype "passive"))
      (node (ref "IC1") (pin "2") (pinfunction "GND_2") (pintype "passive"))
      (node (ref "IC2") (pin "2") (pinfunction "GND_2") (pintype "passive"))
      (node (ref "J1") (pin "1@1") (pinfunction "1_1@1") (pintype "passive"))
      (node (ref "J1") (pin "1@2") (pinfunction "1_1@2") (pintype "passive"))
      (node (ref "J10") (pin "1@1") (pinfunction "1_1@1") (pintype "passive"))
      (node (ref "J10") (pin "1@2") (pinfunction "1_1@2") (pintype "passive"))
      (node (ref "J11") (pin "1@1") (pinfunction "1_1@1") (pintype "passive"))
      (node (ref "J11") (pin "1@2") (pinfunction "1_1@2") (pintype "passive"))
      (node (ref "J2") (pin "1@1") (pinfunction "1_1@1") (pintype "passive"))
      (node (ref "J2") (pin "1@2") (pinfunction "1_1@2") (pintype "passive"))
      (node (ref "J3") (pin "1@1") (pinfunction "1_1@1") (pintype "passive"))
      (node (ref "J3") (pin "1@2") (pinfunction "1_1@2") (pintype "passive"))
      (node (ref "J4") (pin "1@1") (pinfunction "1_1@1") (pintype "passive"))
      (node (ref "J4") (pin "1@2") (pinfunction "1_1@2") (pintype "passive"))
      (node (ref "J5") (pin "1@1") (pinfunction "1_1@1") (pintype "passive"))
      (node (ref "J5") (pin "1@2") (pinfunction "1_1@2") (pintype "passive"))
      (node (ref "J6") (pin "1@1") (pinfunction "1_1@1") (pintype "passive"))
      (node (ref "J6") (pin "1@2") (pinfunction "1_1@2") (pintype "passive"))
      (node (ref "J7") (pin "1@1") (pinfunction "1_1@1") (pintype "passive"))
      (node (ref "J7") (pin "1@2") (pinfunction "1_1@2") (pintype "passive"))
      (node (ref "J8") (pin "1@1") (pinfunction "1_1@1") (pintype "passive"))
      (node (ref "J8") (pin "1@2") (pinfunction "1_1@2") (pintype "passive"))
      (node (ref "J9") (pin "1@1") (pinfunction "1_1@1") (pintype "passive"))
      (node (ref "J9") (pin "1@2") (pinfunction "1_1@2") (pintype "passive"))
      (node (ref "R41") (pin "1") (pinfunction "1_1") (pintype "passive"))
      (node (ref "R42") (pin "1") (pinfunction "1_1") (pintype "passive"))
      (node (ref "R47") (pin "3") (pinfunction "A_3") (pintype "passive"))
      (node (ref "R48") (pin "1") (pinfunction "1_1") (pintype "passive"))
      (node (ref "R49") (pin "1") (pinfunction "1_1") (pintype "passive"))
      (node (ref "SV1") (pin "1") (pinfunction "1_1") (pintype "passive"))
      (node (ref "SV1") (pin "11") (pinfunction "11_11") (pintype "passive"))
      (node (ref "SV1") (pin "13") (pinfunction "13_13") (pintype "passive"))
      (node (ref "SV1") (pin "15") (pinfunction "15_15") (pintype "passive"))
      (node (ref "SV1") (pin "3") (pinfunction "3_3") (pintype "passive"))
      (node (ref "SV1") (pin "5") (pinfunction "5_5") (pintype "passive"))
      (node (ref "SV1") (pin "7") (pinfunction "7_7") (pintype "passive"))
      (node (ref "SV1") (pin "9") (pinfunction "9_9") (pintype "passive"))
      (node (ref "SV2") (pin "1") (pinfunction "1_1") (pintype "passive"))
      (node (ref "SV2") (pin "11") (pinfunction "11_11") (pintype "passive"))
      (node (ref "SV2") (pin "3") (pinfunction "3_3") (pintype "passive"))
      (node (ref "SV2") (pin "5") (pinfunction "5_5") (pintype "passive"))
      (node (ref "SV2") (pin "7") (pinfunction "7_7") (pintype "passive"))
      (node (ref "SV2") (pin "9") (pinfunction "9_9") (pintype "passive"))
      (node (ref "SV3") (pin "3") (pinfunction "3_3") (pintype "passive"))
      (node (ref "SV3") (pin "4") (pinfunction "4_4") (pintype "passive"))
      (node (ref "SV3") (pin "5") (pinfunction "5_5") (pintype "passive"))
      (node (ref "SV3") (pin "6") (pinfunction "6_6") (pintype "passive"))
      (node (ref "SV3") (pin "7") (pinfunction "7_7") (pintype "passive"))
      (node (ref "SV3") (pin "8") (pinfunction "8_8") (pintype "passive"))
      (node (ref "SV4") (pin "3") (pinfunction "3_3") (pintype "passive"))
      (node (ref "SV4") (pin "4") (pinfunction "4_4") (pintype "passive"))
      (node (ref "SV4") (pin "5") (pinfunction "5_5") (pintype "passive"))
      (node (ref "SV4") (pin "6") (pinfunction "6_6") (pintype "passive"))
      (node (ref "SV4") (pin "7") (pinfunction "7_7") (pintype "passive"))
      (node (ref "SV4") (pin "8") (pinfunction "8_8") (pintype "passive"))
      (node (ref "U1") (pin "10") (pinfunction "+IN_10") (pintype "input"))
      (node (ref "U1") (pin "12") (pinfunction "+IN_12") (pintype "input"))
      (node (ref "U1") (pin "3") (pinfunction "+IN_3") (pintype "input"))
      (node (ref "U1") (pin "5") (pinfunction "+IN_5") (pintype "input"))
      (node (ref "U2") (pin "10") (pinfunction "+IN_10") (pintype "input"))
      (node (ref "U2") (pin "12") (pinfunction "+IN_12") (pintype "input"))
      (node (ref "U2") (pin "3") (pinfunction "+IN_3") (pintype "input"))
      (node (ref "U2") (pin "5") (pinfunction "+IN_5") (pintype "input"))
      (node (ref "U3") (pin "10") (pinfunction "+IN_10") (pintype "input"))
      (node (ref "U3") (pin "12") (pinfunction "+IN_12") (pintype "input"))
      (node (ref "U3") (pin "3") (pinfunction "+IN_3") (pintype "input"))
      (node (ref "U3") (pin "5") (pinfunction "+IN_5") (pintype "input"))
      (node (ref "U4") (pin "10") (pinfunction "+IN_10") (pintype "input"))
      (node (ref "U4") (pin "12") (pinfunction "+IN_12") (pintype "input"))
      (node (ref "U4") (pin "3") (pinfunction "+IN_3") (pintype "input"))
      (node (ref "U4") (pin "5") (pinfunction "+IN_5") (pintype "input"))
      (node (ref "U5") (pin "10") (pinfunction "+IN_10") (pintype "input"))
      (node (ref "U5") (pin "12") (pinfunction "+IN_12") (pintype "input"))
      (node (ref "VR1") (pin "P$1") (pinfunction "A_P$1") (pintype "passive"))
      (node (ref "VR2") (pin "P$1") (pinfunction "A_P$1") (pintype "passive"))
      (node (ref "VR3") (pin "P$1") (pinfunction "A_P$1") (pintype "passive"))
      (node (ref "VR4") (pin "P$1") (pinfunction "A_P$1") (pintype "passive"))
      (node (ref "VR5") (pin "P$1") (pinfunction "A_P$1") (pintype "passive"))
      (node (ref "VR6") (pin "P$1") (pinfunction "A_P$1") (pintype "passive"))
      (node (ref "VR7") (pin "P$1") (pinfunction "A_P$1") (pintype "passive"))
    )
    (net (code "15") (name "INL") (class "Default")
      (node (ref "C15") (pin "1") (pinfunction "1_1") (pintype "passive"))
      (node (ref "R39") (pin "1") (pinfunction "1_1") (pintype "passive"))
      (node (ref "R42") (pin "2") (pinfunction "2_2") (pintype "passive"))
      (node (ref "R54") (pin "1") (pinfunction "1_1") (pintype "passive"))
      (node (ref "SV2") (pin "2") (pinfunction "2_2") (pintype "passive"))
    )
    (net (code "16") (name "INR") (class "Default")
      (node (ref "C14") (pin "1") (pinfunction "1_1") (pintype "passive"))
      (node (ref "R38") (pin "1") (pinfunction "1_1") (pintype "passive"))
      (node (ref "R41") (pin "2") (pinfunction "2_2") (pintype "passive"))
      (node (ref "R55") (pin "1") (pinfunction "1_1") (pintype "passive"))
      (node (ref "SV2") (pin "4") (pinfunction "4_4") (pintype "passive"))
    )
    (net (code "17") (name "Net-(D9-PadA)") (class "Default")
      (node (ref "D9") (pin "A") (pinfunction "A_A") (pintype "passive"))
      (node (ref "R43") (pin "2") (pinfunction "2_2") (pintype "passive"))
    )
    (net (code "18") (name "Net-(J7-Pad2)") (class "Default")
      (node (ref "J7") (pin "2") (pinfunction "2_2") (pintype "passive"))
      (node (ref "J8") (pin "3") (pinfunction "3_3") (pintype "passive"))
      (node (ref "R32") (pin "2") (pinfunction "2_2") (pintype "passive"))
    )
    (net (code "19") (name "Net-(J7-Pad3)") (class "Default")
      (node (ref "J7") (pin "3") (pinfunction "3_3") (pintype "passive"))
      (node (ref "R31") (pin "2") (pinfunction "2_2") (pintype "passive"))
    )
    (net (code "20") (name "Net-(Q1-B)") (class "Default")
      (node (ref "Q1") (pin "2") (pinfunction "B_2") (pintype "passive"))
      (node (ref "R44") (pin "2") (pinfunction "2_2") (pintype "passive"))
    )
    (net (code "21") (name "Net-(Q1-C)") (class "Default")
      (node (ref "Q1") (pin "1") (pinfunction "C_1") (pintype "passive"))
      (node (ref "R45") (pin "1") (pinfunction "1_1") (pintype "passive"))
    )
    (net (code "22") (name "Net-(Q1-E)") (class "Default")
      (node (ref "Q1") (pin "3") (pinfunction "E_3") (pintype "passive"))
      (node (ref "R46") (pin "1") (pinfunction "1_1") (pintype "passive"))
    )
    (net (code "23") (name "Net-(R47-E)") (class "Default")
      (node (ref "R46") (pin "2") (pinfunction "2_2") (pintype "passive"))
      (node (ref "R47") (pin "1") (pinfunction "E_1") (pintype "passive"))
      (node (ref "R47") (pin "2") (pinfunction "S_2") (pintype "passive"))
    )
    (net (code "24") (name "Net-(U1A--IN)") (class "Default")
      (node (ref "C1") (pin "1") (pinfunction "1_1") (pintype "passive"))
      (node (ref "R10") (pin "1") (pinfunction "1_1") (pintype "passive"))
      (node (ref "R7") (pin "2") (pinfunction "2_2") (pintype "passive"))
      (node (ref "U1") (pin "2") (pinfunction "-IN_2") (pintype "input"))
    )
    (net (code "25") (name "Net-(U1A-OUT)") (class "Default")
      (node (ref "C1") (pin "2") (pinfunction "2_2") (pintype "passive"))
      (node (ref "R10") (pin "2") (pinfunction "2_2") (pintype "passive"))
      (node (ref "R13") (pin "1") (pinfunction "1_1") (pintype "passive"))
      (node (ref "U1") (pin "1") (pinfunction "OUT_1") (pintype "output"))
    )
    (net (code "26") (name "Net-(U1B--IN)") (class "Default")
      (node (ref "R1") (pin "2") (pinfunction "2_2") (pintype "passive"))
      (node (ref "R4") (pin "1") (pinfunction "1_1") (pintype "passive"))
      (node (ref "U1") (pin "6") (pinfunction "-IN_6") (pintype "input"))
    )
    (net (code "27") (name "Net-(U1B-OUT)") (class "Default")
      (node (ref "R4") (pin "2") (pinfunction "2_2") (pintype "passive"))
      (node (ref "R7") (pin "1") (pinfunction "1_1") (pintype "passive"))
      (node (ref "U1") (pin "7") (pinfunction "OUT_7") (pintype "output"))
    )
    (net (code "28") (name "Net-(U1C--IN)") (class "Default")
      (node (ref "R2") (pin "2") (pinfunction "2_2") (pintype "passive"))
      (node (ref "R5") (pin "1") (pinfunction "1_1") (pintype "passive"))
      (node (ref "U1") (pin "9") (pinfunction "-IN_9") (pintype "input"))
    )
    (net (code "29") (name "Net-(U1C-OUT)") (class "Default")
      (node (ref "R5") (pin "2") (pinfunction "2_2") (pintype "passive"))
      (node (ref "R8") (pin "1") (pinfunction "1_1") (pintype "passive"))
      (node (ref "U1") (pin "8") (pinfunction "OUT_8") (pintype "output"))
    )
    (net (code "30") (name "Net-(U1D--IN)") (class "Default")
      (node (ref "C2") (pin "1") (pinfunction "1_1") (pintype "passive"))
      (node (ref "R11") (pin "1") (pinfunction "1_1") (pintype "passive"))
      (node (ref "R8") (pin "2") (pinfunction "2_2") (pintype "passive"))
      (node (ref "U1") (pin "13") (pinfunction "-IN_13") (pintype "input"))
    )
    (net (code "31") (name "Net-(U1D-OUT)") (class "Default")
      (node (ref "C2") (pin "2") (pinfunction "2_2") (pintype "passive"))
      (node (ref "R11") (pin "2") (pinfunction "2_2") (pintype "passive"))
      (node (ref "R14") (pin "1") (pinfunction "1_1") (pintype "passive"))
      (node (ref "U1") (pin "14") (pinfunction "OUT_14") (pintype "output"))
    )
    (net (code "32") (name "Net-(U2A--IN)") (class "Default")
      (node (ref "C3") (pin "1") (pinfunction "1_1") (pintype "passive"))
      (node (ref "R12") (pin "1") (pinfunction "1_1") (pintype "passive"))
      (node (ref "R9") (pin "2") (pinfunction "2_2") (pintype "passive"))
      (node (ref "U2") (pin "2") (pinfunction "-IN_2") (pintype "input"))
    )
    (net (code "33") (name "Net-(U2A-OUT)") (class "Default")
      (node (ref "C3") (pin "2") (pinfunction "2_2") (pintype "passive"))
      (node (ref "R12") (pin "2") (pinfunction "2_2") (pintype "passive"))
      (node (ref "R15") (pin "1") (pinfunction "1_1") (pintype "passive"))
      (node (ref "U2") (pin "1") (pinfunction "OUT_1") (pintype "output"))
    )
    (net (code "34") (name "Net-(U2B--IN)") (class "Default")
      (node (ref "R3") (pin "2") (pinfunction "2_2") (pintype "passive"))
      (node (ref "R6") (pin "1") (pinfunction "1_1") (pintype "passive"))
      (node (ref "U2") (pin "6") (pinfunction "-IN_6") (pintype "input"))
    )
    (net (code "35") (name "Net-(U2B-OUT)") (class "Default")
      (node (ref "R6") (pin "2") (pinfunction "2_2") (pintype "passive"))
      (node (ref "R9") (pin "1") (pinfunction "1_1") (pintype "passive"))
      (node (ref "U2") (pin "7") (pinfunction "OUT_7") (pintype "output"))
    )
    (net (code "36") (name "Net-(U2C--IN)") (class "Default")
      (node (ref "R16") (pin "2") (pinfunction "2_2") (pintype "passive"))
      (node (ref "R19") (pin "1") (pinfunction "1_1") (pintype "passive"))
      (node (ref "U2") (pin "9") (pinfunction "-IN_9") (pintype "input"))
    )
    (net (code "37") (name "Net-(U2C-OUT)") (class "Default")
      (node (ref "R19") (pin "2") (pinfunction "2_2") (pintype "passive"))
      (node (ref "R22") (pin "1") (pinfunction "1_1") (pintype "passive"))
      (node (ref "U2") (pin "8") (pinfunction "OUT_8") (pintype "output"))
    )
    (net (code "38") (name "Net-(U2D--IN)") (class "Default")
      (node (ref "C7") (pin "1") (pinfunction "1_1") (pintype "passive"))
      (node (ref "R22") (pin "2") (pinfunction "2_2") (pintype "passive"))
      (node (ref "R25") (pin "1") (pinfunction "1_1") (pintype "passive"))
      (node (ref "U2") (pin "13") (pinfunction "-IN_13") (pintype "input"))
    )
    (net (code "39") (name "Net-(U2D-OUT)") (class "Default")
      (node (ref "C7") (pin "2") (pinfunction "2_2") (pintype "passive"))
      (node (ref "R25") (pin "2") (pinfunction "2_2") (pintype "passive"))
      (node (ref "R28") (pin "1") (pinfunction "1_1") (pintype "passive"))
      (node (ref "U2") (pin "14") (pinfunction "OUT_14") (pintype "output"))
    )
    (net (code "40") (name "Net-(U3A--IN)") (class "Default")
      (node (ref "C8") (pin "1") (pinfunction "1_1") (pintype "passive"))
      (node (ref "R23") (pin "2") (pinfunction "2_2") (pintype "passive"))
      (node (ref "R26") (pin "1") (pinfunction "1_1") (pintype "passive"))
      (node (ref "U3") (pin "2") (pinfunction "-IN_2") (pintype "input"))
    )
    (net (code "41") (name "Net-(U3A-OUT)") (class "Default")
      (node (ref "C8") (pin "2") (pinfunction "2_2") (pintype "passive"))
      (node (ref "R26") (pin "2") (pinfunction "2_2") (pintype "passive"))
      (node (ref "R29") (pin "1") (pinfunction "1_1") (pintype "passive"))
      (node (ref "U3") (pin "1") (pinfunction "OUT_1") (pintype "output"))
    )
    (net (code "42") (name "Net-(U3B--IN)") (class "Default")
      (node (ref "R17") (pin "2") (pinfunction "2_2") (pintype "passive"))
      (node (ref "R20") (pin "1") (pinfunction "1_1") (pintype "passive"))
      (node (ref "U3") (pin "6") (pinfunction "-IN_6") (pintype "input"))
    )
    (net (code "43") (name "Net-(U3B-OUT)") (class "Default")
      (node (ref "R20") (pin "2") (pinfunction "2_2") (pintype "passive"))
      (node (ref "R23") (pin "1") (pinfunction "1_1") (pintype "passive"))
      (node (ref "U3") (pin "7") (pinfunction "OUT_7") (pintype "output"))
    )
    (net (code "44") (name "Net-(U3C--IN)") (class "Default")
      (node (ref "R18") (pin "2") (pinfunction "2_2") (pintype "passive"))
      (node (ref "R21") (pin "1") (pinfunction "1_1") (pintype "passive"))
      (node (ref "U3") (pin "9") (pinfunction "-IN_9") (pintype "input"))
    )
    (net (code "45") (name "Net-(U3C-OUT)") (class "Default")
      (node (ref "R21") (pin "2") (pinfunction "2_2") (pintype "passive"))
      (node (ref "R24") (pin "1") (pinfunction "1_1") (pintype "passive"))
      (node (ref "U3") (pin "8") (pinfunction "OUT_8") (pintype "output"))
    )
    (net (code "46") (name "Net-(U3D--IN)") (class "Default")
      (node (ref "C9") (pin "1") (pinfunction "1_1") (pintype "passive"))
      (node (ref "R24") (pin "2") (pinfunction "2_2") (pintype "passive"))
      (node (ref "R27") (pin "1") (pinfunction "1_1") (pintype "passive"))
      (node (ref "U3") (pin "13") (pinfunction "-IN_13") (pintype "input"))
    )
    (net (code "47") (name "Net-(U3D-OUT)") (class "Default")
      (node (ref "C9") (pin "2") (pinfunction "2_2") (pintype "passive"))
      (node (ref "R27") (pin "2") (pinfunction "2_2") (pintype "passive"))
      (node (ref "R30") (pin "1") (pinfunction "1_1") (pintype "passive"))
      (node (ref "U3") (pin "14") (pinfunction "OUT_14") (pintype "output"))
    )
    (net (code "48") (name "Net-(U4A--IN)") (class "Default")
      (node (ref "R31") (pin "1") (pinfunction "1_1") (pintype "passive"))
      (node (ref "R34") (pin "2") (pinfunction "2_2") (pintype "passive"))
      (node (ref "U4") (pin "2") (pinfunction "-IN_2") (pintype "input"))
    )
    (net (code "49") (name "Net-(U4A-OUT)") (class "Default")
      (node (ref "R38") (pin "2") (pinfunction "2_2") (pintype "passive"))
      (node (ref "U4") (pin "1") (pinfunction "OUT_1") (pintype "output"))
      (node (ref "VR8") (pin "A2") (pinfunction "S_A2") (pintype "passive"))
      (node (ref "VR8") (pin "A3") (pinfunction "E_A3") (pintype "passive"))
    )
    (net (code "50") (name "Net-(U4B--IN)") (class "Default")
      (node (ref "R32") (pin "1") (pinfunction "1_1") (pintype "passive"))
      (node (ref "R35") (pin "2") (pinfunction "2_2") (pintype "passive"))
      (node (ref "U4") (pin "6") (pinfunction "-IN_6") (pintype "input"))
    )
    (net (code "51") (name "Net-(U4B-OUT)") (class "Default")
      (node (ref "R39") (pin "2") (pinfunction "2_2") (pintype "passive"))
      (node (ref "U4") (pin "7") (pinfunction "OUT_7") (pintype "output"))
      (node (ref "VR8") (pin "B2") (pinfunction "S_B2") (pintype "passive"))
      (node (ref "VR8") (pin "B3") (pinfunction "E_B3") (pintype "passive"))
    )
    (net (code "52") (name "Net-(U4C--IN)") (class "Default")
      (node (ref "C16") (pin "1") (pinfunction "1_1") (pintype "passive"))
      (node (ref "R50") (pin "1") (pinfunction "1_1") (pintype "passive"))
      (node (ref "R52") (pin "2") (pinfunction "2_2") (pintype "passive"))
      (node (ref "U4") (pin "9") (pinfunction "-IN_9") (pintype "input"))
    )
    (net (code "53") (name "Net-(U4C-OUT)") (class "Default")
      (node (ref "C16") (pin "2") (pinfunction "2_2") (pintype "passive"))
      (node (ref "R52") (pin "1") (pinfunction "1_1") (pintype "passive"))
      (node (ref "R56") (pin "2") (pinfunction "2_2") (pintype "passive"))
      (node (ref "U4") (pin "8") (pinfunction "OUT_8") (pintype "output"))
    )
    (net (code "54") (name "Net-(U4D--IN)") (class "Default")
      (node (ref "C17") (pin "1") (pinfunction "1_1") (pintype "passive"))
      (node (ref "R51") (pin "1") (pinfunction "1_1") (pintype "passive"))
      (node (ref "R53") (pin "2") (pinfunction "2_2") (pintype "passive"))
      (node (ref "U4") (pin "13") (pinfunction "-IN_13") (pintype "input"))
    )
    (net (code "55") (name "Net-(U4D-OUT)") (class "Default")
      (node (ref "C17") (pin "2") (pinfunction "2_2") (pintype "passive"))
      (node (ref "R53") (pin "1") (pinfunction "1_1") (pintype "passive"))
      (node (ref "R57") (pin "2") (pinfunction "2_2") (pintype "passive"))
      (node (ref "U4") (pin "14") (pinfunction "OUT_14") (pintype "output"))
    )
    (net (code "56") (name "Net-(U5A-+IN)") (class "Default")
      (node (ref "C19") (pin "1") (pinfunction "1_1") (pintype "passive"))
      (node (ref "R55") (pin "2") (pinfunction "2_2") (pintype "passive"))
      (node (ref "U5") (pin "3") (pinfunction "+IN_3") (pintype "input"))
      (node (ref "V2") (pin "4") (pinfunction "RES2_4") (pintype "passive"))
    )
    (net (code "57") (name "Net-(U5A--IN)") (class "Default")
      (node (ref "J11") (pin "3") (pinfunction "3_3") (pintype "passive"))
      (node (ref "R59") (pin "2") (pinfunction "2_2") (pintype "passive"))
      (node (ref "U5") (pin "2") (pinfunction "-IN_2") (pintype "input"))
    )
    (net (code "58") (name "Net-(U5A-OUT)") (class "Default")
      (node (ref "R59") (pin "1") (pinfunction "1_1") (pintype "passive"))
      (node (ref "U5") (pin "1") (pinfunction "OUT_1") (pintype "output"))
    )
    (net (code "59") (name "Net-(U5B-+IN)") (class "Default")
      (node (ref "C18") (pin "1") (pinfunction "1_1") (pintype "passive"))
      (node (ref "R54") (pin "2") (pinfunction "2_2") (pintype "passive"))
      (node (ref "U5") (pin "5") (pinfunction "+IN_5") (pintype "input"))
      (node (ref "V1") (pin "4") (pinfunction "RES2_4") (pintype "passive"))
    )
    (net (code "60") (name "Net-(U5B--IN)") (class "Default")
      (node (ref "J10") (pin "3") (pinfunction "3_3") (pintype "passive"))
      (node (ref "R58") (pin "2") (pinfunction "2_2") (pintype "passive"))
      (node (ref "U5") (pin "6") (pinfunction "-IN_6") (pintype "input"))
    )
    (net (code "61") (name "Net-(U5B-OUT)") (class "Default")
      (node (ref "R58") (pin "1") (pinfunction "1_1") (pintype "passive"))
      (node (ref "U5") (pin "7") (pinfunction "OUT_7") (pintype "output"))
    )
    (net (code "62") (name "Net-(U5C--IN)") (class "Default")
      (node (ref "C13") (pin "1") (pinfunction "1_1") (pintype "passive"))
      (node (ref "R37") (pin "2") (pinfunction "2_2") (pintype "passive"))
      (node (ref "R40") (pin "1") (pinfunction "1_1") (pintype "passive"))
      (node (ref "U5") (pin "9") (pinfunction "-IN_9") (pintype "input"))
    )
    (net (code "63") (name "Net-(U5C-OUT)") (class "Default")
      (node (ref "C13") (pin "2") (pinfunction "2_2") (pintype "passive"))
      (node (ref "R40") (pin "2") (pinfunction "2_2") (pintype "passive"))
      (node (ref "R43") (pin "1") (pinfunction "1_1") (pintype "passive"))
      (node (ref "R44") (pin "1") (pinfunction "1_1") (pintype "passive"))
      (node (ref "U5") (pin "8") (pinfunction "OUT_8") (pintype "output"))
    )
    (net (code "64") (name "Net-(U5D--IN)") (class "Default")
      (node (ref "R33") (pin "2") (pinfunction "2_2") (pintype "passive"))
      (node (ref "R36") (pin "1") (pinfunction "1_1") (pintype "passive"))
      (node (ref "U5") (pin "13") (pinfunction "-IN_13") (pintype "input"))
    )
    (net (code "65") (name "Net-(U5D-OUT)") (class "Default")
      (node (ref "R36") (pin "2") (pinfunction "2_2") (pintype "passive"))
      (node (ref "R37") (pin "1") (pinfunction "1_1") (pintype "passive"))
      (node (ref "U5") (pin "14") (pinfunction "OUT_14") (pintype "output"))
    )
    (net (code "66") (name "Net-(VR1-E)") (class "Default")
      (node (ref "J1") (pin "3") (pinfunction "3_3") (pintype "passive"))
      (node (ref "VR1") (pin "P$3") (pinfunction "E_P$3") (pintype "passive"))
    )
    (net (code "67") (name "Net-(VR1-S)") (class "Default")
      (node (ref "R1") (pin "1") (pinfunction "1_1") (pintype "passive"))
      (node (ref "VR1") (pin "P$2") (pinfunction "S_P$2") (pintype "passive"))
    )
    (net (code "68") (name "Net-(VR2-E)") (class "Default")
      (node (ref "J2") (pin "3") (pinfunction "3_3") (pintype "passive"))
      (node (ref "VR2") (pin "P$3") (pinfunction "E_P$3") (pintype "passive"))
    )
    (net (code "69") (name "Net-(VR2-S)") (class "Default")
      (node (ref "R2") (pin "1") (pinfunction "1_1") (pintype "passive"))
      (node (ref "VR2") (pin "P$2") (pinfunction "S_P$2") (pintype "passive"))
    )
    (net (code "70") (name "Net-(VR3-E)") (class "Default")
      (node (ref "J3") (pin "3") (pinfunction "3_3") (pintype "passive"))
      (node (ref "VR3") (pin "P$3") (pinfunction "E_P$3") (pintype "passive"))
    )
    (net (code "71") (name "Net-(VR3-S)") (class "Default")
      (node (ref "R3") (pin "1") (pinfunction "1_1") (pintype "passive"))
      (node (ref "VR3") (pin "P$2") (pinfunction "S_P$2") (pintype "passive"))
    )
    (net (code "72") (name "Net-(VR4-E)") (class "Default")
      (node (ref "J4") (pin "3") (pinfunction "3_3") (pintype "passive"))
      (node (ref "VR4") (pin "P$3") (pinfunction "E_P$3") (pintype "passive"))
    )
    (net (code "73") (name "Net-(VR4-S)") (class "Default")
      (node (ref "R16") (pin "1") (pinfunction "1_1") (pintype "passive"))
      (node (ref "VR4") (pin "P$2") (pinfunction "S_P$2") (pintype "passive"))
    )
    (net (code "74") (name "Net-(VR5-E)") (class "Default")
      (node (ref "J5") (pin "3") (pinfunction "3_3") (pintype "passive"))
      (node (ref "VR5") (pin "P$3") (pinfunction "E_P$3") (pintype "passive"))
    )
    (net (code "75") (name "Net-(VR5-S)") (class "Default")
      (node (ref "R17") (pin "1") (pinfunction "1_1") (pintype "passive"))
      (node (ref "VR5") (pin "P$2") (pinfunction "S_P$2") (pintype "passive"))
    )
    (net (code "76") (name "Net-(VR6-E)") (class "Default")
      (node (ref "J6") (pin "3") (pinfunction "3_3") (pintype "passive"))
      (node (ref "VR6") (pin "P$3") (pinfunction "E_P$3") (pintype "passive"))
    )
    (net (code "77") (name "Net-(VR6-S)") (class "Default")
      (node (ref "R18") (pin "1") (pinfunction "1_1") (pintype "passive"))
      (node (ref "VR6") (pin "P$2") (pinfunction "S_P$2") (pintype "passive"))
    )
    (net (code "78") (name "Net-(VR7-E)") (class "Default")
      (node (ref "J9") (pin "3") (pinfunction "3_3") (pintype "passive"))
      (node (ref "VR7") (pin "P$3") (pinfunction "E_P$3") (pintype "passive"))
    )
    (net (code "79") (name "Net-(VR7-S)") (class "Default")
      (node (ref "R33") (pin "1") (pinfunction "1_1") (pintype "passive"))
      (node (ref "VR7") (pin "P$2") (pinfunction "S_P$2") (pintype "passive"))
    )
    (net (code "80") (name "Net-(VR8A-A)") (class "Default")
      (node (ref "R34") (pin "1") (pinfunction "1_1") (pintype "passive"))
      (node (ref "VR8") (pin "A1") (pinfunction "A_A1") (pintype "passive"))
    )
    (net (code "81") (name "Net-(VR8B-A)") (class "Default")
      (node (ref "R35") (pin "1") (pinfunction "1_1") (pintype "passive"))
      (node (ref "VR8") (pin "B1") (pinfunction "A_B1") (pintype "passive"))
    )
    (net (code "82") (name "OUTL") (class "Default")
      (node (ref "R49") (pin "2") (pinfunction "2_2") (pintype "passive"))
      (node (ref "R51") (pin "2") (pinfunction "2_2") (pintype "passive"))
      (node (ref "SV2") (pin "10") (pinfunction "10_10") (pintype "passive"))
    )
    (net (code "83") (name "OUTR") (class "Default")
      (node (ref "R48") (pin "2") (pinfunction "2_2") (pintype "passive"))
      (node (ref "R50") (pin "2") (pinfunction "2_2") (pintype "passive"))
      (node (ref "SV2") (pin "12") (pinfunction "12_12") (pintype "passive"))
    )
    (net (code "84") (name "VDD") (class "Default")
      (node (ref "D7") (pin "A") (pinfunction "A_A") (pintype "passive"))
      (node (ref "SV3") (pin "10") (pinfunction "10_10") (pintype "passive"))
      (node (ref "SV3") (pin "9") (pinfunction "9_9") (pintype "passive"))
    )
    (net (code "85") (name "VSS") (class "Default")
      (node (ref "D8") (pin "C") (pinfunction "C_C") (pintype "passive"))
      (node (ref "SV3") (pin "1") (pinfunction "1_1") (pintype "passive"))
      (node (ref "SV3") (pin "2") (pinfunction "2_2") (pintype "passive"))
    )
    (net (code "86") (name "WET_L") (class "Default")
      (node (ref "R57") (pin "1") (pinfunction "1_1") (pintype "passive"))
      (node (ref "V1") (pin "3") (pinfunction "RES1_3") (pintype "passive"))
    )
    (net (code "87") (name "WET_R") (class "Default")
      (node (ref "R56") (pin "1") (pinfunction "1_1") (pintype "passive"))
      (node (ref "V2") (pin "3") (pinfunction "RES1_3") (pintype "passive"))
    )
    (net (code "88") (name "unconnected-(J8-Pad2)") (class "Default")
      (node (ref "J8") (pin "2") (pinfunction "2_2") (pintype "passive"))
    )
    (net (code "89") (name "unconnected-(J10-Pad2)") (class "Default")
      (node (ref "J10") (pin "2") (pinfunction "2_2") (pintype "passive"))
    )
    (net (code "90") (name "unconnected-(J11-Pad2)") (class "Default")
      (node (ref "J11") (pin "2") (pinfunction "2_2") (pintype "passive"))
    )
    (net (code "91") (name "unconnected-(SV2-Pad6)") (class "Default")
      (node (ref "SV2") (pin "6") (pinfunction "6_6") (pintype "passive"))
    )
    (net (code "92") (name "unconnected-(SV2-Pad8)") (class "Default")
      (node (ref "SV2") (pin "8") (pinfunction "8_8") (pintype "passive"))
    )
  )
)
